# 07_ADC.net
KiCad netlist of a schematic drawn in Altium Designer
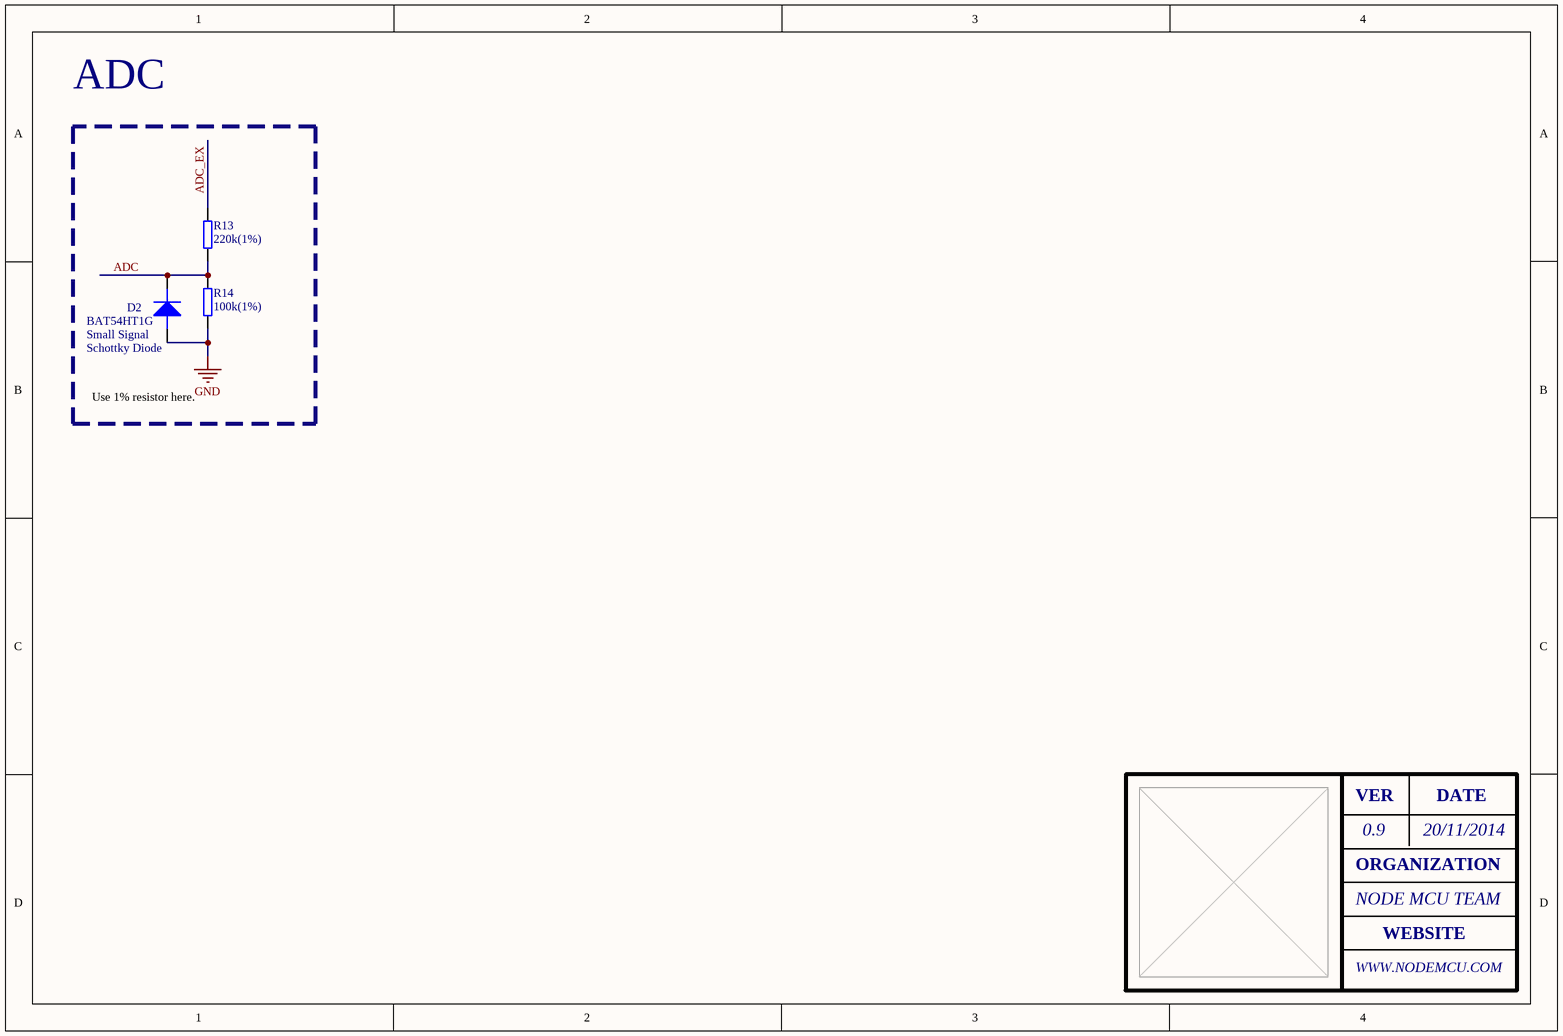
[diagram p0: 07_ADC.SchDoc]

(export (version "E")
  (design (tool "Eeschema 10.0.6"))
  (components
    (comp (ref "D2")
      (value "BAT54HT1G")
      (footprint "SOD-323 2L")
      (description "FAIRCHILD SEMICONDUCTOR - BAT54HT1G - DIODE, SCHOTTKY, 30V, SOD-323")
      (fields (field (name "MANUFACTURER") "FAIRCHILD SEMICONDUCTOR"))
      (libsource (lib "Diodes") (part "BAT54HT1G"))
    )
    (comp (ref "R13")
      (value "220k(1%)")
      (footprint "SMT_R_0402")
      (description "Surface mount resistor 0402")
      (libsource (lib "Vowstar_Basic_Device") (part "SMT_R_0402"))
    )
    (comp (ref "R14")
      (value "100k(1%)")
      (footprint "SMT_R_0402")
      (description "Surface mount resistor 0402")
      (libsource (lib "Vowstar_Basic_Device") (part "SMT_R_0402"))
    )
  )
  (nets
    (net (code "1") (name "/ADC") (class "Default")
      (node (ref "D2") (pin "1") (pinfunction "cathode_1") (pintype "passive"))
      (node (ref "R13") (pin "1") (pinfunction "1_1") (pintype "passive"))
      (node (ref "R14") (pin "2") (pinfunction "2_2") (pintype "passive"))
    )
    (net (code "2") (name "/ADC_EX") (class "Default")
      (node (ref "R13") (pin "2") (pinfunction "2_2") (pintype "passive"))
    )
    (net (code "3") (name "GND") (class "Default")
      (node (ref "D2") (pin "2") (pinfunction "ANODE_2") (pintype "passive"))
      (node (ref "R14") (pin "1") (pinfunction "1_1") (pintype "passive"))
    )
  )
)
